# FaBo_KeyBoard_Sample_cursor_Rev100000.net
KiCad netlist of a schematic drawn in EAGLE
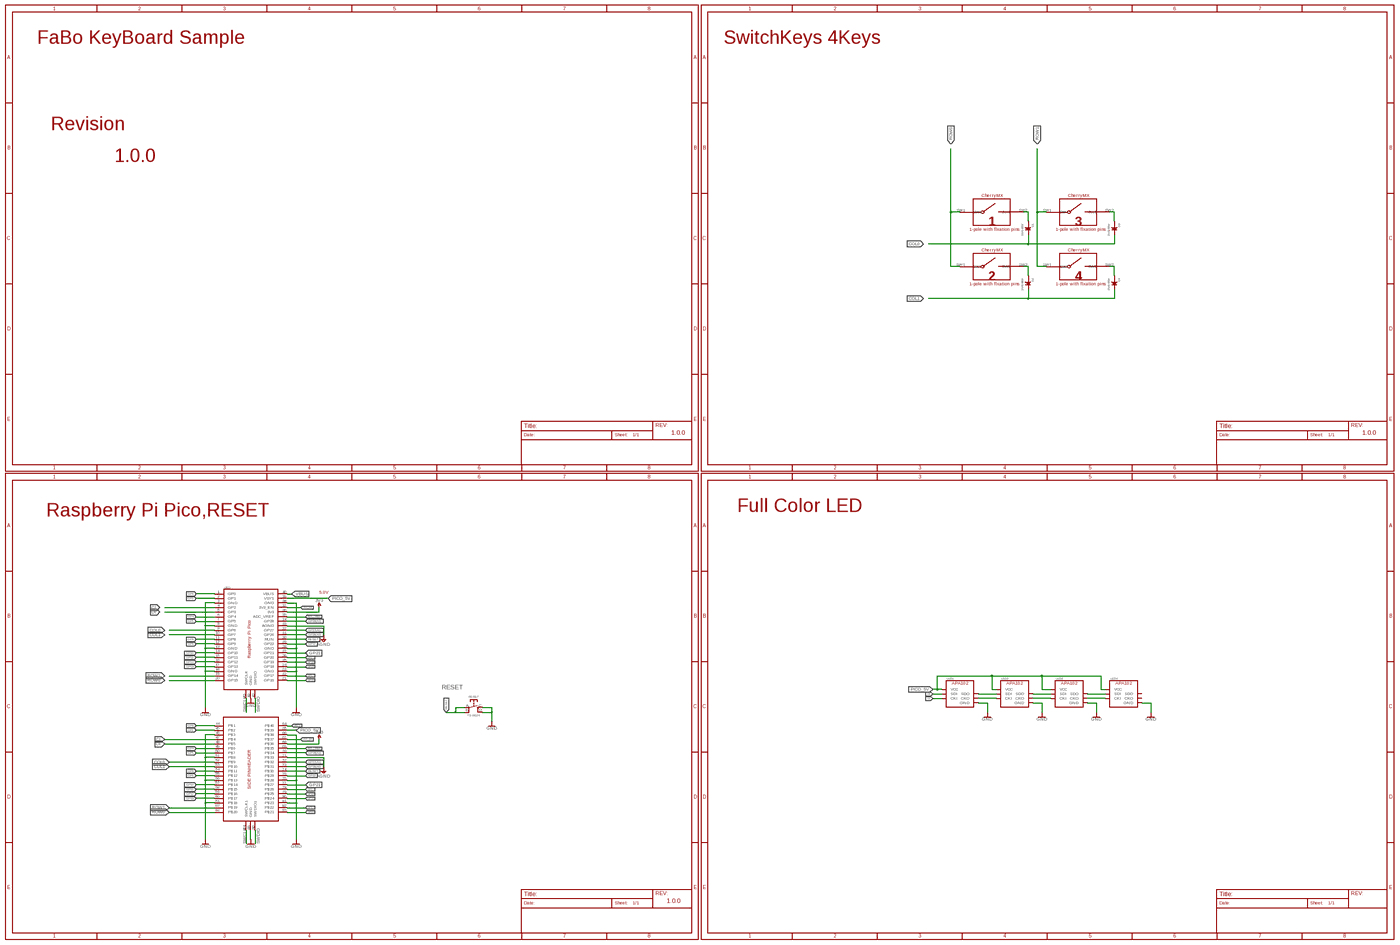
[diagram p0: schematic, sheet 1, overview]
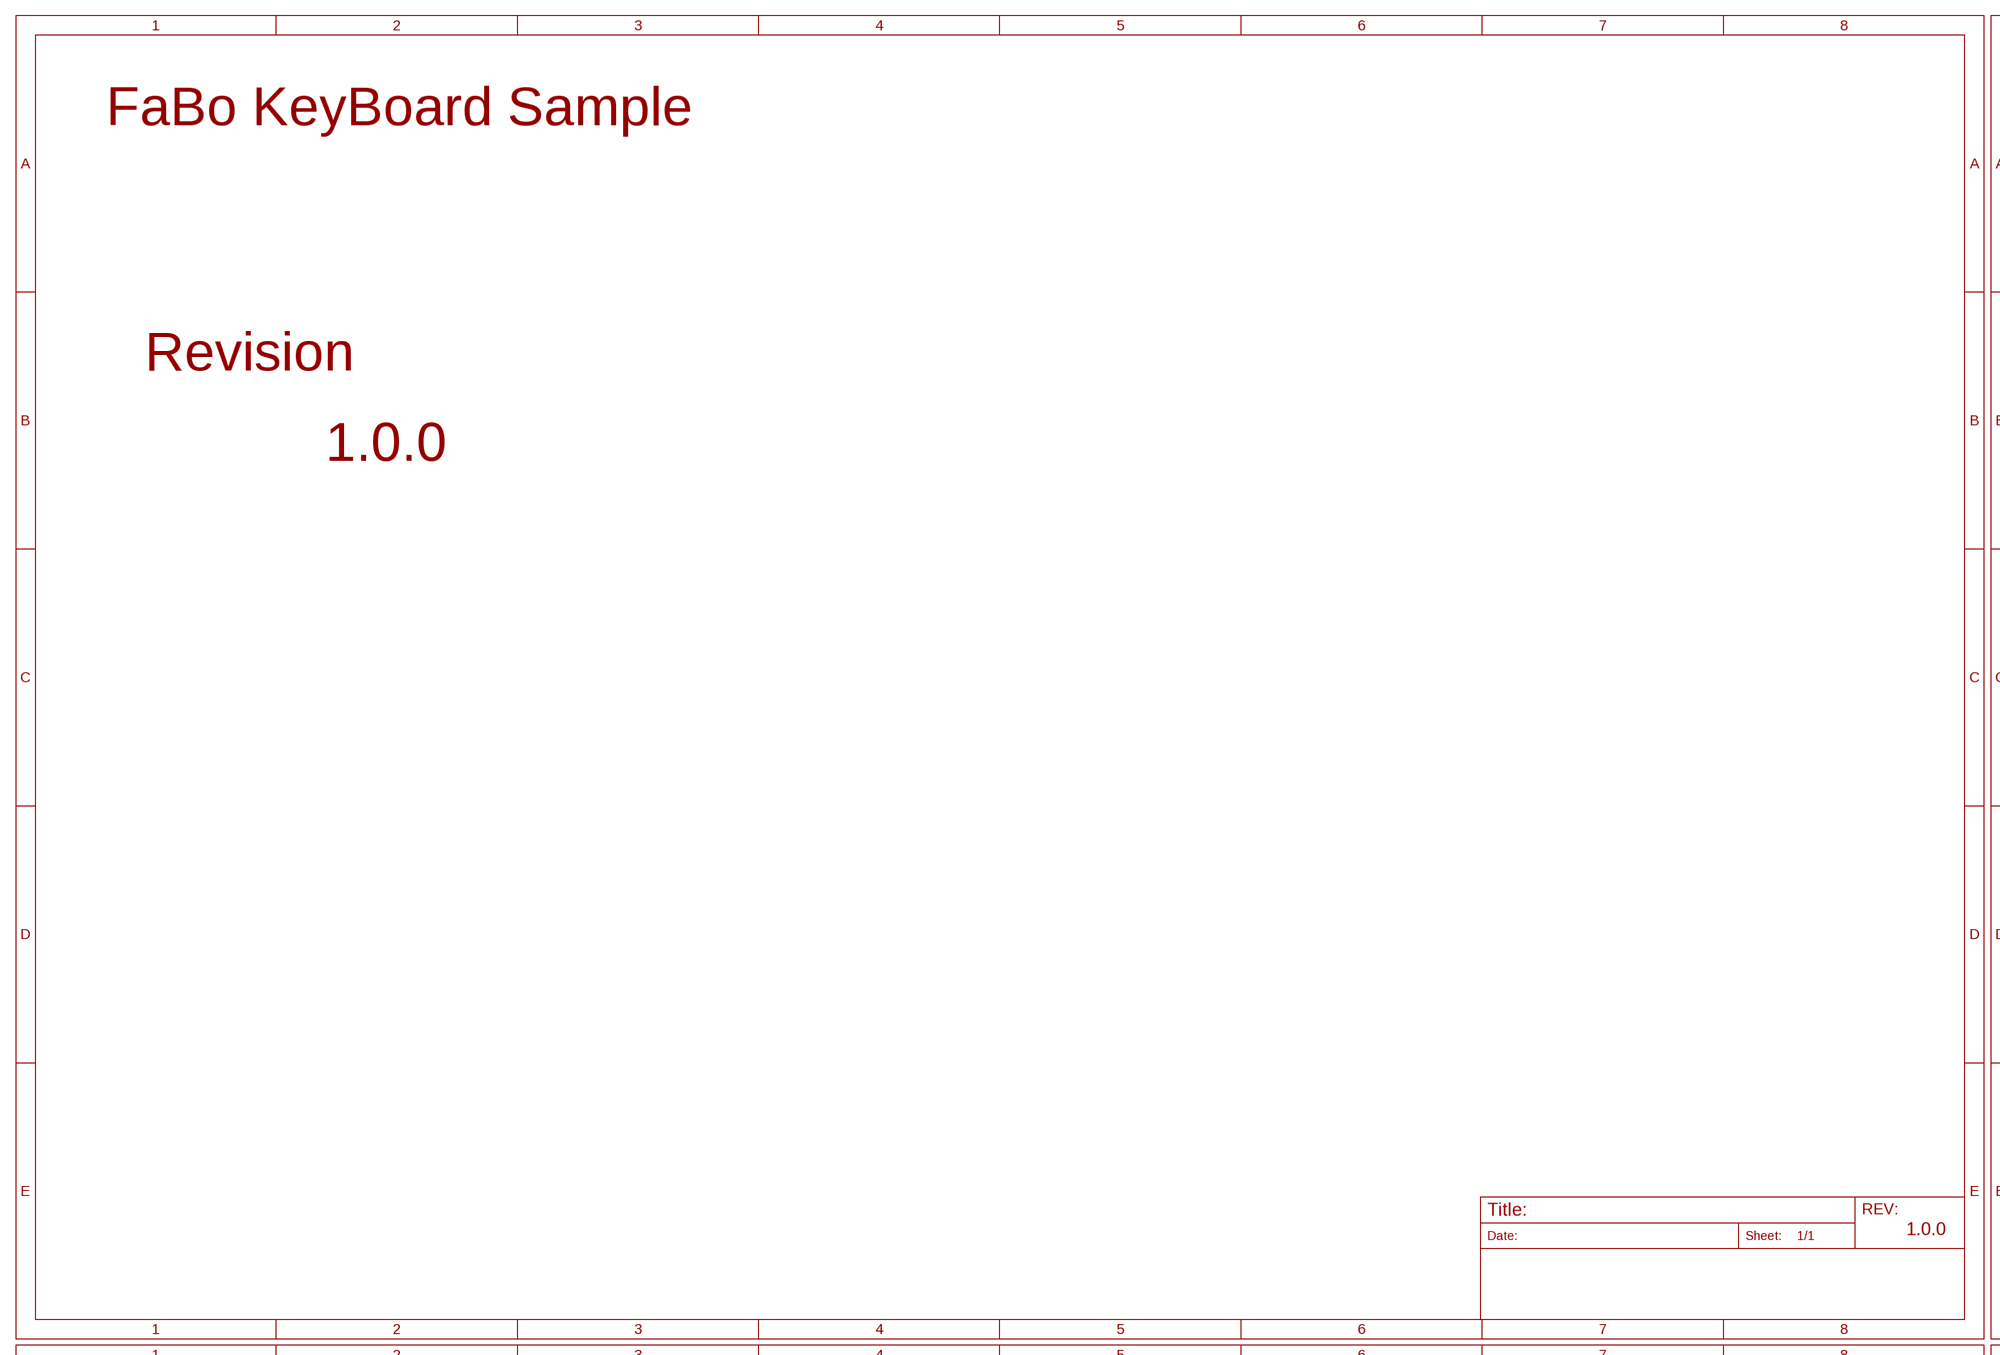
[diagram p1: schematic, sheet 1, part 1 of 4]
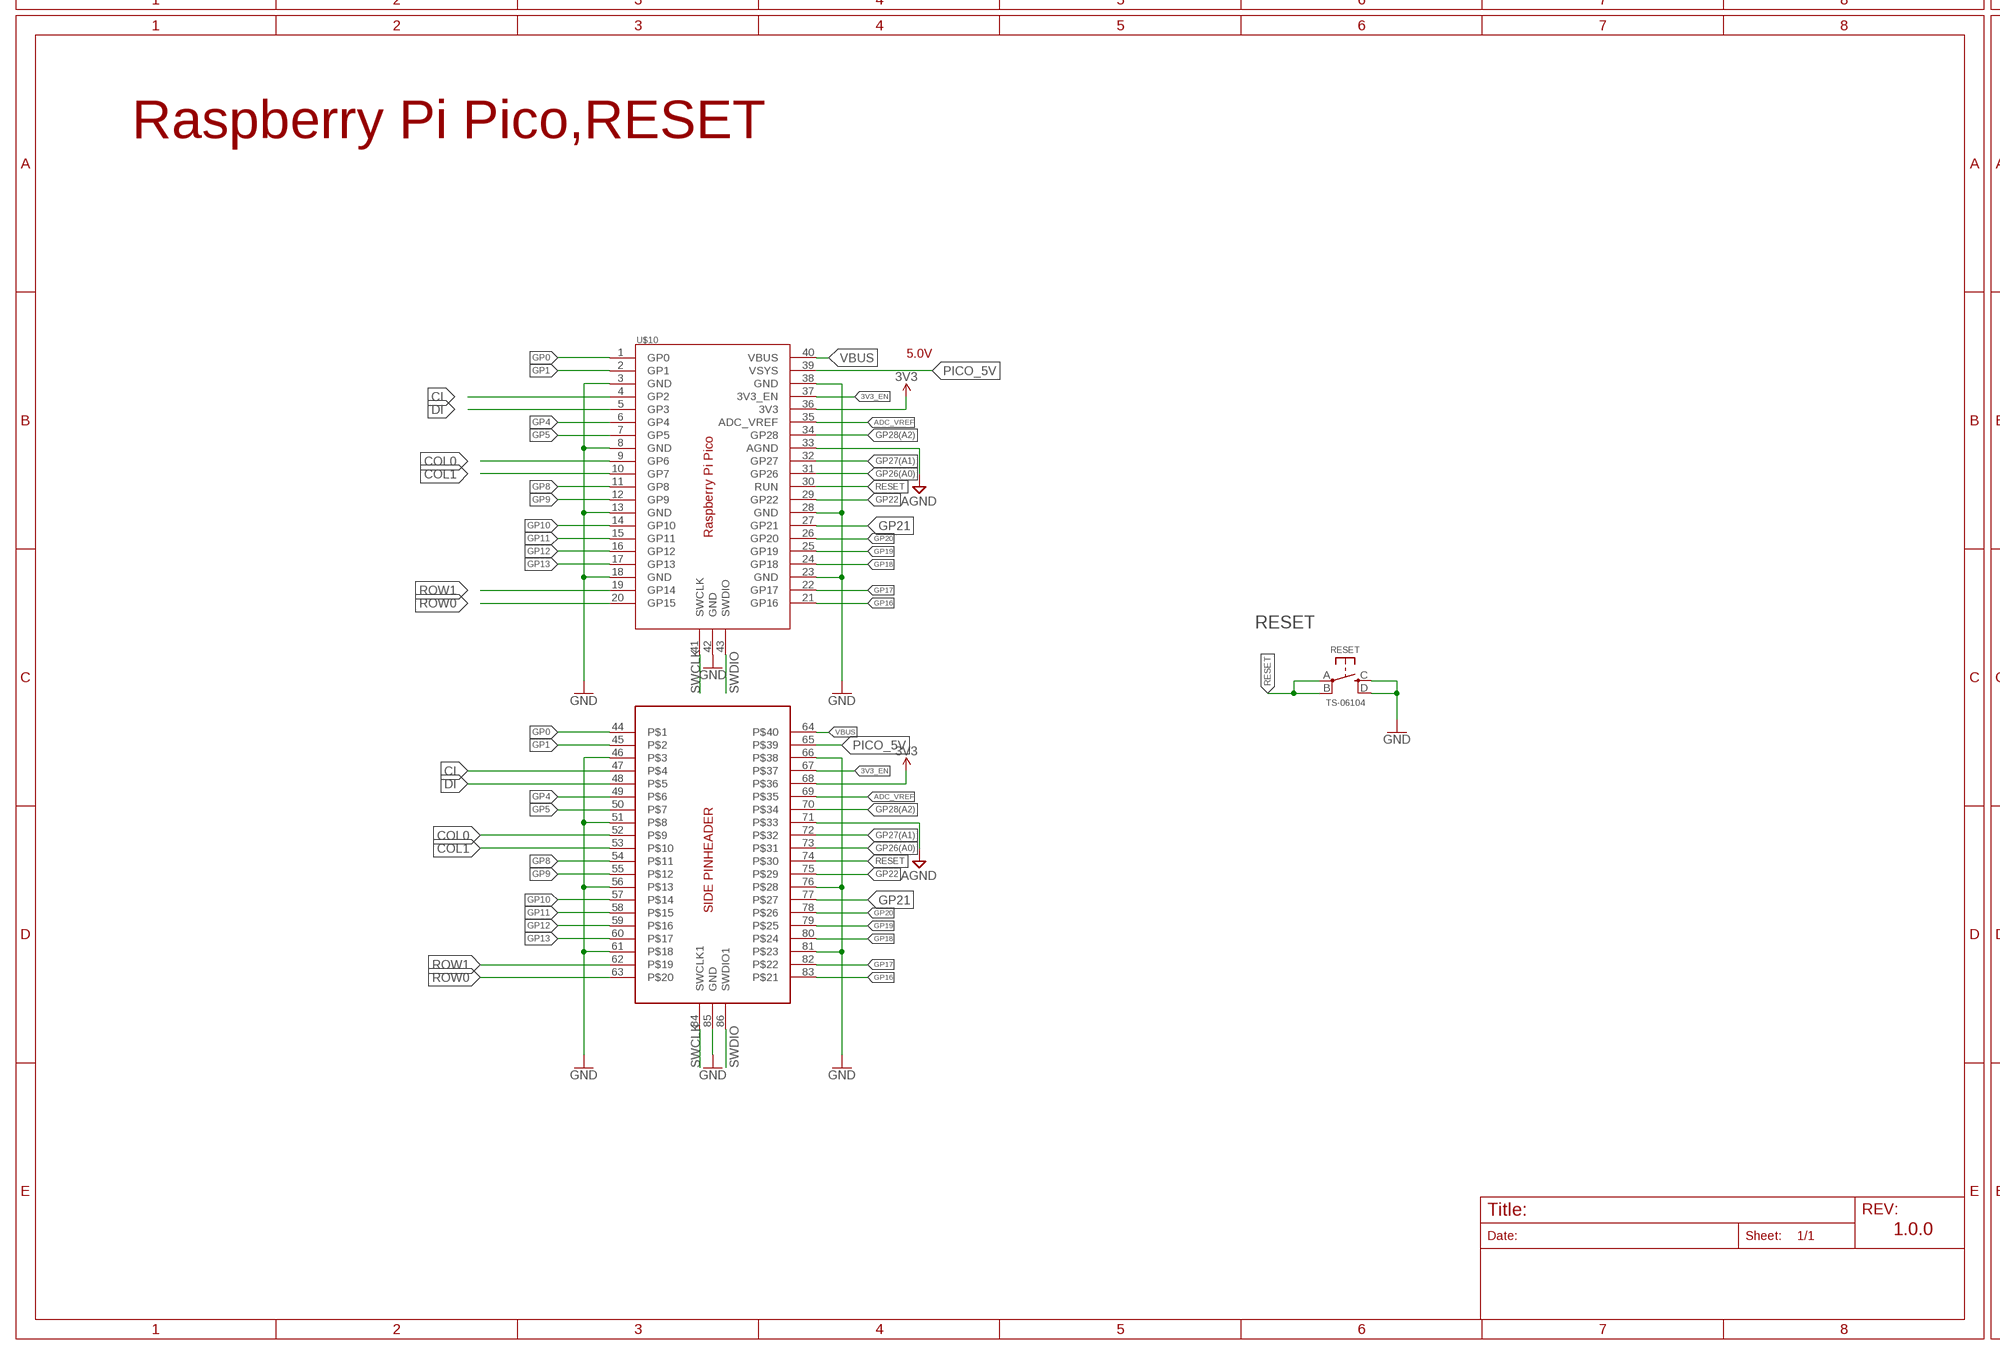
[diagram p2: schematic, sheet 1, part 2 of 4]
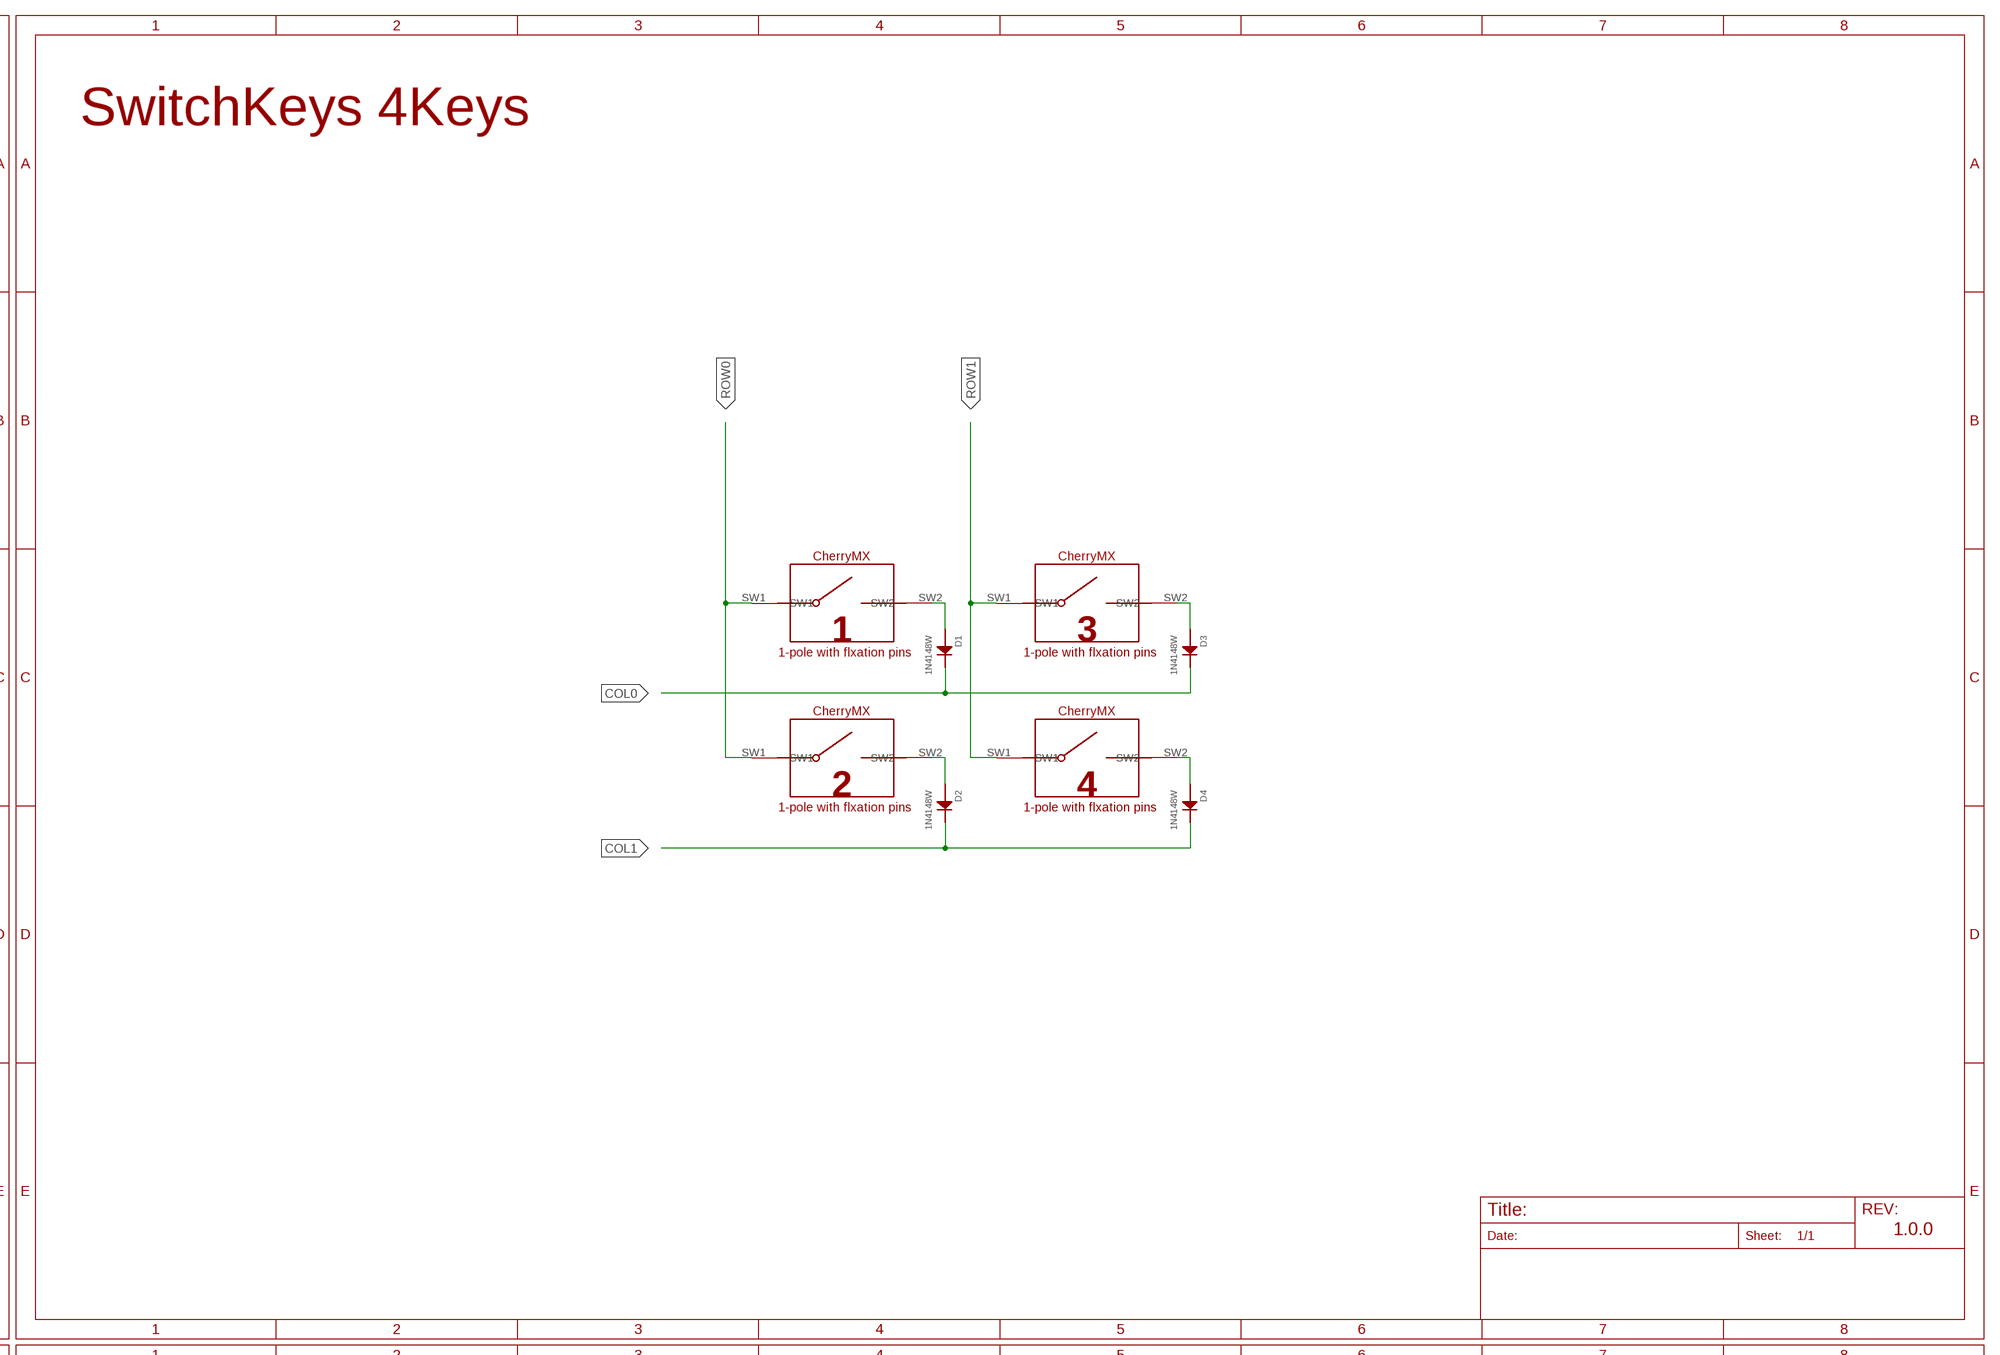
[diagram p3: schematic, sheet 1, part 3 of 4]
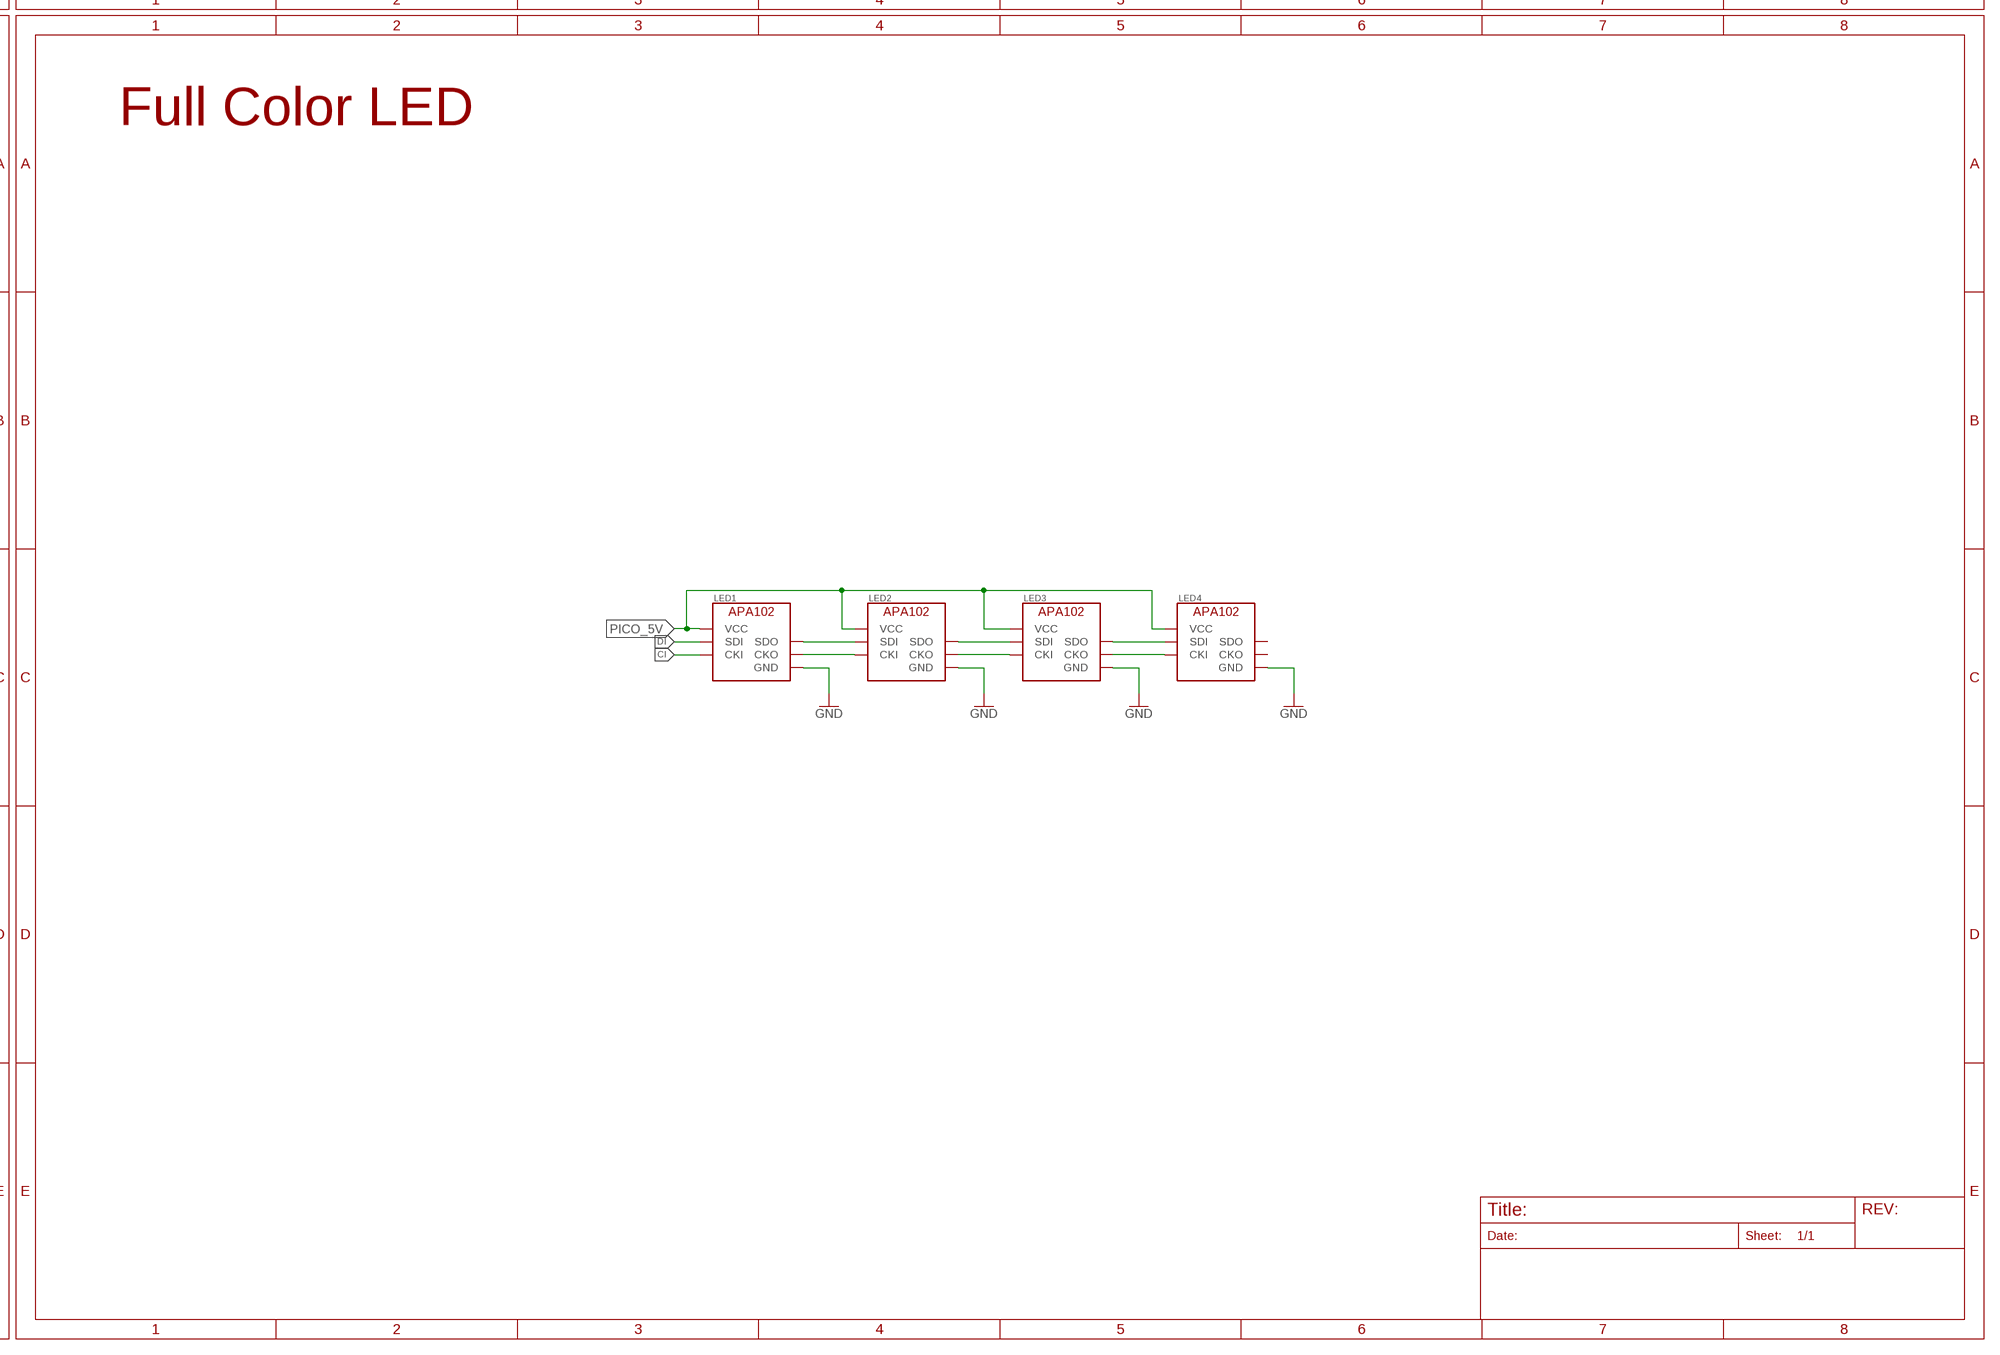
[diagram p4: schematic, sheet 1, part 4 of 4]

(export (version "E")
  (design (tool "Eeschema 10.0.6"))
  (components
    (comp (ref "D1")
      (value "1N4148W")
      (footprint "eagle-import:SOD-123")
      (libsource (lib "eagle-import") (part "1N4148W"))
    )
    (comp (ref "D2")
      (value "1N4148W")
      (footprint "eagle-import:SOD-123")
      (libsource (lib "eagle-import") (part "1N4148W"))
    )
    (comp (ref "D3")
      (value "1N4148W")
      (footprint "eagle-import:SOD-123")
      (libsource (lib "eagle-import") (part "1N4148W"))
    )
    (comp (ref "D4")
      (value "1N4148W")
      (footprint "eagle-import:SOD-123")
      (libsource (lib "eagle-import") (part "1N4148W"))
    )
    (comp (ref "LED1")
      (value "APA102_IPIXEL")
      (footprint "eagle-import:APA102_2020")
      (libsource (lib "eagle-import") (part "APA102_IPIXEL"))
    )
    (comp (ref "LED2")
      (value "APA102_IPIXEL")
      (footprint "eagle-import:APA102_2020")
      (libsource (lib "eagle-import") (part "APA102_IPIXEL"))
    )
    (comp (ref "LED3")
      (value "APA102_IPIXEL")
      (footprint "eagle-import:APA102_2020")
      (libsource (lib "eagle-import") (part "APA102_IPIXEL"))
    )
    (comp (ref "LED4")
      (value "APA102_IPIXEL")
      (footprint "eagle-import:APA102_2020")
      (libsource (lib "eagle-import") (part "APA102_IPIXEL"))
    )
    (comp (ref "RESET")
      (value "TS-06104")
      (footprint "eagle-import:TS-06104")
      (libsource (lib "eagle-import") (part "TS-06104"))
    )
    (comp (ref "SW1")
      (value "CHERRYMX_1-POLE_FLXATION_PINS")
      (footprint "eagle-import:CHERRYMX_1-POLE_FLXATION_PINS")
      (libsource (lib "eagle-import") (part "CHERRYMX_1-POLE_FLXATION_PINS"))
    )
    (comp (ref "SW2")
      (value "CHERRYMX_1-POLE_FLXATION_PINS")
      (footprint "eagle-import:CHERRYMX_1-POLE_FLXATION_PINS")
      (libsource (lib "eagle-import") (part "CHERRYMX_1-POLE_FLXATION_PINS"))
    )
    (comp (ref "SW3")
      (value "CHERRYMX_1-POLE_FLXATION_PINS")
      (footprint "eagle-import:CHERRYMX_1-POLE_FLXATION_PINS")
      (libsource (lib "eagle-import") (part "CHERRYMX_1-POLE_FLXATION_PINS"))
    )
    (comp (ref "SW4")
      (value "CHERRYMX_1-POLE_FLXATION_PINS")
      (footprint "eagle-import:CHERRYMX_1-POLE_FLXATION_PINS")
      (libsource (lib "eagle-import") (part "CHERRYMX_1-POLE_FLXATION_PINS"))
    )
    (comp (ref "U$10")
      (value "RASPBERRY_PI_PICO_BOTH_TH_PINHEADER")
      (footprint "eagle-import:RASPBERRY_PI_PICO_HEADER_BOTH")
      (libsource (lib "eagle-import") (part "RASPBERRY_PI_PICO_BOTH_TH_PINHEADER"))
    )
  )
  (nets
    (net (code "1") (name "/SWCLK") (class "Default")
      (node (ref "U$10") (pin "41") (pinfunction "SWCLK_41") (pintype "bidirectional"))
      (node (ref "U$10") (pin "84") (pinfunction "SWCLK1_84") (pintype "bidirectional"))
    )
    (net (code "2") (name "/SWDIO") (class "Default")
      (node (ref "U$10") (pin "43") (pinfunction "SWDIO_43") (pintype "bidirectional"))
      (node (ref "U$10") (pin "86") (pinfunction "SWDIO1_86") (pintype "bidirectional"))
    )
    (net (code "3") (name "3V3") (class "Default")
      (node (ref "U$10") (pin "36") (pinfunction "3V3_36") (pintype "bidirectional"))
      (node (ref "U$10") (pin "68") (pinfunction "P$36_68") (pintype "bidirectional"))
    )
    (net (code "4") (name "3V3_EN") (class "Default")
      (node (ref "U$10") (pin "37") (pinfunction "3V3_EN_37") (pintype "bidirectional"))
      (node (ref "U$10") (pin "67") (pinfunction "P$37_67") (pintype "bidirectional"))
    )
    (net (code "5") (name "ADC_VREF") (class "Default")
      (node (ref "U$10") (pin "35") (pinfunction "ADC_VREF_35") (pintype "bidirectional"))
      (node (ref "U$10") (pin "69") (pinfunction "P$35_69") (pintype "bidirectional"))
    )
    (net (code "6") (name "AGND") (class "Default")
      (node (ref "U$10") (pin "33") (pinfunction "AGND_33") (pintype "bidirectional"))
      (node (ref "U$10") (pin "71") (pinfunction "P$33_71") (pintype "bidirectional"))
    )
    (net (code "7") (name "CI") (class "Default")
      (node (ref "LED1") (pin "CKI") (pinfunction "CKI_CKI") (pintype "bidirectional"))
      (node (ref "U$10") (pin "4") (pinfunction "GP2_4") (pintype "bidirectional"))
      (node (ref "U$10") (pin "47") (pinfunction "P$4_47") (pintype "bidirectional"))
    )
    (net (code "8") (name "COL0") (class "Default")
      (node (ref "D1") (pin "1") (pinfunction "CATHODE_1") (pintype "bidirectional"))
      (node (ref "D3") (pin "1") (pinfunction "CATHODE_1") (pintype "bidirectional"))
      (node (ref "U$10") (pin "52") (pinfunction "P$9_52") (pintype "bidirectional"))
      (node (ref "U$10") (pin "9") (pinfunction "GP6_9") (pintype "bidirectional"))
    )
    (net (code "9") (name "COL1") (class "Default")
      (node (ref "D2") (pin "1") (pinfunction "CATHODE_1") (pintype "bidirectional"))
      (node (ref "D4") (pin "1") (pinfunction "CATHODE_1") (pintype "bidirectional"))
      (node (ref "U$10") (pin "10") (pinfunction "GP7_10") (pintype "bidirectional"))
      (node (ref "U$10") (pin "53") (pinfunction "P$10_53") (pintype "bidirectional"))
    )
    (net (code "10") (name "DI") (class "Default")
      (node (ref "LED1") (pin "SDI") (pinfunction "SDI_SDI") (pintype "bidirectional"))
      (node (ref "U$10") (pin "48") (pinfunction "P$5_48") (pintype "bidirectional"))
      (node (ref "U$10") (pin "5") (pinfunction "GP3_5") (pintype "bidirectional"))
    )
    (net (code "11") (name "GND") (class "Default")
      (node (ref "LED1") (pin "GND") (pinfunction "GND_GND") (pintype "bidirectional"))
      (node (ref "LED2") (pin "GND") (pinfunction "GND_GND") (pintype "bidirectional"))
      (node (ref "LED3") (pin "GND") (pinfunction "GND_GND") (pintype "bidirectional"))
      (node (ref "LED4") (pin "GND") (pinfunction "GND_GND") (pintype "bidirectional"))
      (node (ref "RESET") (pin "C") (pinfunction "C_C") (pintype "passive"))
      (node (ref "RESET") (pin "D") (pinfunction "D_D") (pintype "passive"))
      (node (ref "U$10") (pin "13") (pinfunction "GND_13") (pintype "bidirectional"))
      (node (ref "U$10") (pin "18") (pinfunction "GND_18") (pintype "bidirectional"))
      (node (ref "U$10") (pin "23") (pinfunction "GND_23") (pintype "bidirectional"))
      (node (ref "U$10") (pin "28") (pinfunction "GND_28") (pintype "bidirectional"))
      (node (ref "U$10") (pin "3") (pinfunction "GND_3") (pintype "bidirectional"))
      (node (ref "U$10") (pin "38") (pinfunction "GND_38") (pintype "bidirectional"))
      (node (ref "U$10") (pin "42") (pinfunction "GND_42") (pintype "bidirectional"))
      (node (ref "U$10") (pin "46") (pinfunction "P$3_46") (pintype "bidirectional"))
      (node (ref "U$10") (pin "51") (pinfunction "P$8_51") (pintype "bidirectional"))
      (node (ref "U$10") (pin "56") (pinfunction "P$13_56") (pintype "bidirectional"))
      (node (ref "U$10") (pin "61") (pinfunction "P$18_61") (pintype "bidirectional"))
      (node (ref "U$10") (pin "66") (pinfunction "P$38_66") (pintype "bidirectional"))
      (node (ref "U$10") (pin "76") (pinfunction "P$28_76") (pintype "bidirectional"))
      (node (ref "U$10") (pin "8") (pinfunction "GND_8") (pintype "bidirectional"))
      (node (ref "U$10") (pin "81") (pinfunction "P$23_81") (pintype "bidirectional"))
      (node (ref "U$10") (pin "85") (pinfunction "GND_85") (pintype "bidirectional"))
    )
    (net (code "12") (name "GP0") (class "Default")
      (node (ref "U$10") (pin "1") (pinfunction "GP0_1") (pintype "bidirectional"))
      (node (ref "U$10") (pin "44") (pinfunction "P$1_44") (pintype "bidirectional"))
    )
    (net (code "13") (name "GP1") (class "Default")
      (node (ref "U$10") (pin "2") (pinfunction "GP1_2") (pintype "bidirectional"))
      (node (ref "U$10") (pin "45") (pinfunction "P$2_45") (pintype "bidirectional"))
    )
    (net (code "14") (name "GP4") (class "Default")
      (node (ref "U$10") (pin "49") (pinfunction "P$6_49") (pintype "bidirectional"))
      (node (ref "U$10") (pin "6") (pinfunction "GP4_6") (pintype "bidirectional"))
    )
    (net (code "15") (name "GP5") (class "Default")
      (node (ref "U$10") (pin "50") (pinfunction "P$7_50") (pintype "bidirectional"))
      (node (ref "U$10") (pin "7") (pinfunction "GP5_7") (pintype "bidirectional"))
    )
    (net (code "16") (name "GP8") (class "Default")
      (node (ref "U$10") (pin "11") (pinfunction "GP8_11") (pintype "bidirectional"))
      (node (ref "U$10") (pin "54") (pinfunction "P$11_54") (pintype "bidirectional"))
    )
    (net (code "17") (name "GP9") (class "Default")
      (node (ref "U$10") (pin "12") (pinfunction "GP9_12") (pintype "bidirectional"))
      (node (ref "U$10") (pin "55") (pinfunction "P$12_55") (pintype "bidirectional"))
    )
    (net (code "18") (name "GP10") (class "Default")
      (node (ref "U$10") (pin "14") (pinfunction "GP10_14") (pintype "bidirectional"))
      (node (ref "U$10") (pin "57") (pinfunction "P$14_57") (pintype "bidirectional"))
    )
    (net (code "19") (name "GP11") (class "Default")
      (node (ref "U$10") (pin "15") (pinfunction "GP11_15") (pintype "bidirectional"))
      (node (ref "U$10") (pin "58") (pinfunction "P$15_58") (pintype "bidirectional"))
    )
    (net (code "20") (name "GP12") (class "Default")
      (node (ref "U$10") (pin "16") (pinfunction "GP12_16") (pintype "bidirectional"))
      (node (ref "U$10") (pin "59") (pinfunction "P$16_59") (pintype "bidirectional"))
    )
    (net (code "21") (name "GP13") (class "Default")
      (node (ref "U$10") (pin "17") (pinfunction "GP13_17") (pintype "bidirectional"))
      (node (ref "U$10") (pin "60") (pinfunction "P$17_60") (pintype "bidirectional"))
    )
    (net (code "22") (name "GP16") (class "Default")
      (node (ref "U$10") (pin "21") (pinfunction "GP16_21") (pintype "bidirectional"))
      (node (ref "U$10") (pin "83") (pinfunction "P$21_83") (pintype "bidirectional"))
    )
    (net (code "23") (name "GP17") (class "Default")
      (node (ref "U$10") (pin "22") (pinfunction "GP17_22") (pintype "bidirectional"))
      (node (ref "U$10") (pin "82") (pinfunction "P$22_82") (pintype "bidirectional"))
    )
    (net (code "24") (name "GP18") (class "Default")
      (node (ref "U$10") (pin "24") (pinfunction "GP18_24") (pintype "bidirectional"))
      (node (ref "U$10") (pin "80") (pinfunction "P$24_80") (pintype "bidirectional"))
    )
    (net (code "25") (name "GP19") (class "Default")
      (node (ref "U$10") (pin "25") (pinfunction "GP19_25") (pintype "bidirectional"))
      (node (ref "U$10") (pin "79") (pinfunction "P$25_79") (pintype "bidirectional"))
    )
    (net (code "26") (name "GP20") (class "Default")
      (node (ref "U$10") (pin "26") (pinfunction "GP20_26") (pintype "bidirectional"))
      (node (ref "U$10") (pin "78") (pinfunction "P$26_78") (pintype "bidirectional"))
    )
    (net (code "27") (name "GP21") (class "Default")
      (node (ref "U$10") (pin "27") (pinfunction "GP21_27") (pintype "bidirectional"))
      (node (ref "U$10") (pin "77") (pinfunction "P$27_77") (pintype "bidirectional"))
    )
    (net (code "28") (name "GP22") (class "Default")
      (node (ref "U$10") (pin "29") (pinfunction "GP22_29") (pintype "bidirectional"))
      (node (ref "U$10") (pin "75") (pinfunction "P$29_75") (pintype "bidirectional"))
    )
    (net (code "29") (name "GP26(A0)") (class "Default")
      (node (ref "U$10") (pin "31") (pinfunction "GP26_31") (pintype "bidirectional"))
      (node (ref "U$10") (pin "73") (pinfunction "P$31_73") (pintype "bidirectional"))
    )
    (net (code "30") (name "GP27(A1)") (class "Default")
      (node (ref "U$10") (pin "32") (pinfunction "GP27_32") (pintype "bidirectional"))
      (node (ref "U$10") (pin "72") (pinfunction "P$32_72") (pintype "bidirectional"))
    )
    (net (code "31") (name "GP28(A2)") (class "Default")
      (node (ref "U$10") (pin "34") (pinfunction "GP28_34") (pintype "bidirectional"))
      (node (ref "U$10") (pin "70") (pinfunction "P$34_70") (pintype "bidirectional"))
    )
    (net (code "32") (name "Net-(D1-ANODE)") (class "Default")
      (node (ref "D1") (pin "2") (pinfunction "ANODE_2") (pintype "bidirectional"))
      (node (ref "SW1") (pin "SW2") (pinfunction "SW2_SW2") (pintype "bidirectional"))
    )
    (net (code "33") (name "Net-(D2-ANODE)") (class "Default")
      (node (ref "D2") (pin "2") (pinfunction "ANODE_2") (pintype "bidirectional"))
      (node (ref "SW2") (pin "SW2") (pinfunction "SW2_SW2") (pintype "bidirectional"))
    )
    (net (code "34") (name "Net-(D3-ANODE)") (class "Default")
      (node (ref "D3") (pin "2") (pinfunction "ANODE_2") (pintype "bidirectional"))
      (node (ref "SW3") (pin "SW2") (pinfunction "SW2_SW2") (pintype "bidirectional"))
    )
    (net (code "35") (name "Net-(D4-ANODE)") (class "Default")
      (node (ref "D4") (pin "2") (pinfunction "ANODE_2") (pintype "bidirectional"))
      (node (ref "SW4") (pin "SW2") (pinfunction "SW2_SW2") (pintype "bidirectional"))
    )
    (net (code "36") (name "Net-(LED1-PadCKO)") (class "Default")
      (node (ref "LED1") (pin "CKO") (pinfunction "CKO_CKO") (pintype "bidirectional"))
      (node (ref "LED2") (pin "CKI") (pinfunction "CKI_CKI") (pintype "bidirectional"))
    )
    (net (code "37") (name "Net-(LED1-PadSDO)") (class "Default")
      (node (ref "LED1") (pin "SDO") (pinfunction "SDO_SDO") (pintype "bidirectional"))
      (node (ref "LED2") (pin "SDI") (pinfunction "SDI_SDI") (pintype "bidirectional"))
    )
    (net (code "38") (name "Net-(LED2-PadCKO)") (class "Default")
      (node (ref "LED2") (pin "CKO") (pinfunction "CKO_CKO") (pintype "bidirectional"))
      (node (ref "LED3") (pin "CKI") (pinfunction "CKI_CKI") (pintype "bidirectional"))
    )
    (net (code "39") (name "Net-(LED2-PadSDO)") (class "Default")
      (node (ref "LED2") (pin "SDO") (pinfunction "SDO_SDO") (pintype "bidirectional"))
      (node (ref "LED3") (pin "SDI") (pinfunction "SDI_SDI") (pintype "bidirectional"))
    )
    (net (code "40") (name "Net-(LED3-PadCKO)") (class "Default")
      (node (ref "LED3") (pin "CKO") (pinfunction "CKO_CKO") (pintype "bidirectional"))
      (node (ref "LED4") (pin "CKI") (pinfunction "CKI_CKI") (pintype "bidirectional"))
    )
    (net (code "41") (name "Net-(LED3-PadSDO)") (class "Default")
      (node (ref "LED3") (pin "SDO") (pinfunction "SDO_SDO") (pintype "bidirectional"))
      (node (ref "LED4") (pin "SDI") (pinfunction "SDI_SDI") (pintype "bidirectional"))
    )
    (net (code "42") (name "PICO_5V") (class "Default")
      (node (ref "LED1") (pin "VCC") (pinfunction "VCC_VCC") (pintype "bidirectional"))
      (node (ref "LED2") (pin "VCC") (pinfunction "VCC_VCC") (pintype "bidirectional"))
      (node (ref "LED3") (pin "VCC") (pinfunction "VCC_VCC") (pintype "bidirectional"))
      (node (ref "LED4") (pin "VCC") (pinfunction "VCC_VCC") (pintype "bidirectional"))
      (node (ref "U$10") (pin "39") (pinfunction "VSYS_39") (pintype "bidirectional"))
      (node (ref "U$10") (pin "65") (pinfunction "P$39_65") (pintype "bidirectional"))
    )
    (net (code "43") (name "RESET") (class "Default")
      (node (ref "RESET") (pin "A") (pinfunction "A_A") (pintype "passive"))
      (node (ref "RESET") (pin "B") (pinfunction "B_B") (pintype "passive"))
      (node (ref "U$10") (pin "30") (pinfunction "RUN_30") (pintype "bidirectional"))
      (node (ref "U$10") (pin "74") (pinfunction "P$30_74") (pintype "bidirectional"))
    )
    (net (code "44") (name "ROW0") (class "Default")
      (node (ref "SW1") (pin "SW1") (pinfunction "SW1_SW1") (pintype "bidirectional"))
      (node (ref "SW2") (pin "SW1") (pinfunction "SW1_SW1") (pintype "bidirectional"))
      (node (ref "U$10") (pin "20") (pinfunction "GP15_20") (pintype "bidirectional"))
      (node (ref "U$10") (pin "63") (pinfunction "P$20_63") (pintype "bidirectional"))
    )
    (net (code "45") (name "ROW1") (class "Default")
      (node (ref "SW3") (pin "SW1") (pinfunction "SW1_SW1") (pintype "bidirectional"))
      (node (ref "SW4") (pin "SW1") (pinfunction "SW1_SW1") (pintype "bidirectional"))
      (node (ref "U$10") (pin "19") (pinfunction "GP14_19") (pintype "bidirectional"))
      (node (ref "U$10") (pin "62") (pinfunction "P$19_62") (pintype "bidirectional"))
    )
    (net (code "46") (name "VBUS") (class "Default")
      (node (ref "U$10") (pin "40") (pinfunction "VBUS_40") (pintype "bidirectional"))
      (node (ref "U$10") (pin "64") (pinfunction "P$40_64") (pintype "bidirectional"))
    )
    (net (code "47") (name "unconnected-(LED4-PadCKO)") (class "Default")
      (node (ref "LED4") (pin "CKO") (pinfunction "CKO_CKO") (pintype "bidirectional"))
    )
    (net (code "48") (name "unconnected-(LED4-PadSDO)") (class "Default")
      (node (ref "LED4") (pin "SDO") (pinfunction "SDO_SDO") (pintype "bidirectional"))
    )
  )
)
